# protection.net
KiCad netlist of a schematic drawn in Altium Designer
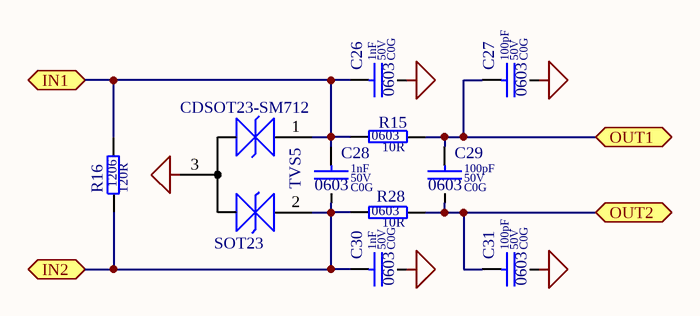
[diagram p0: protection.SchDoc]

(export (version "E")
  (design (tool "Eeschema 10.0.6"))
  (components
    (comp (ref "C26")
      (value "1nF")
      (footprint "C_0603_1608")
      (description "Capacitor")
      (fields
        (field (name "DIELECTRIC") "C0G")
        (field (name "VOLTAGE") "50V")
        (field (name "SCH_FOOTPRINT") "0603")
        (field (name "PART NUMBER") "C_1nF_50V_C0G_0603_5")
        (field (name "MANUFACTURER") "Samsung")
      )
      (libsource (lib "Library") (part "C"))
    )
    (comp (ref "C27")
      (value "100pF")
      (footprint "C_0603_1608")
      (description "Capacitor")
      (fields
        (field (name "DIELECTRIC") "C0G")
        (field (name "VOLTAGE") "50V")
        (field (name "SCH_FOOTPRINT") "0603")
        (field (name "PART NUMBER") "C_100pF_50V_C0G_0603_5")
        (field (name "MANUFACTURER") "AVX")
      )
      (libsource (lib "Library") (part "C"))
    )
    (comp (ref "C28")
      (value "1nF")
      (footprint "C_0603_1608")
      (description "Capacitor")
      (fields
        (field (name "DIELECTRIC") "C0G")
        (field (name "VOLTAGE") "50V")
        (field (name "SCH_FOOTPRINT") "0603")
        (field (name "PART NUMBER") "C_1nF_50V_C0G_0603_5")
        (field (name "MANUFACTURER") "Samsung")
      )
      (libsource (lib "Library") (part "C"))
    )
    (comp (ref "C29")
      (value "100pF")
      (footprint "C_0603_1608")
      (description "Capacitor")
      (fields
        (field (name "DIELECTRIC") "C0G")
        (field (name "VOLTAGE") "50V")
        (field (name "SCH_FOOTPRINT") "0603")
        (field (name "PART NUMBER") "C_100pF_50V_C0G_0603_5")
        (field (name "MANUFACTURER") "AVX")
      )
      (libsource (lib "Library") (part "C"))
    )
    (comp (ref "C30")
      (value "1nF")
      (footprint "C_0603_1608")
      (description "Capacitor")
      (fields
        (field (name "DIELECTRIC") "C0G")
        (field (name "VOLTAGE") "50V")
        (field (name "SCH_FOOTPRINT") "0603")
        (field (name "PART NUMBER") "C_1nF_50V_C0G_0603_5")
        (field (name "MANUFACTURER") "Samsung")
      )
      (libsource (lib "Library") (part "C"))
    )
    (comp (ref "C31")
      (value "100pF")
      (footprint "C_0603_1608")
      (description "Capacitor")
      (fields
        (field (name "DIELECTRIC") "C0G")
        (field (name "VOLTAGE") "50V")
        (field (name "SCH_FOOTPRINT") "0603")
        (field (name "PART NUMBER") "C_100pF_50V_C0G_0603_5")
        (field (name "MANUFACTURER") "AVX")
      )
      (libsource (lib "Library") (part "C"))
    )
    (comp (ref "R15")
      (value "10R")
      (footprint "R_0603_1608")
      (fields
        (field (name "SCH_FOOTPRINT") "0603")
        (field (name "PART NUMBER") "R_10R_0603_1")
        (field (name "VOLTAGE") "50V")
        (field (name "POWER") "100mW")
      )
      (libsource (lib "Library") (part "R"))
    )
    (comp (ref "R16")
      (value "120R")
      (footprint "R_1206_3216")
      (fields
        (field (name "SCH_FOOTPRINT") "1206")
        (field (name "PART NUMBER") "R_120R_1206_1")
        (field (name "VOLTAGE") "200V")
        (field (name "POWER") "250mW")
      )
      (libsource (lib "") (part "R_1"))
    )
    (comp (ref "R28")
      (value "10R")
      (footprint "R_0603_1608")
      (fields
        (field (name "SCH_FOOTPRINT") "0603")
        (field (name "PART NUMBER") "R_10R_0603_1")
        (field (name "VOLTAGE") "50V")
        (field (name "POWER") "100mW")
      )
      (libsource (lib "Library") (part "R"))
    )
    (comp (ref "TVS5")
      (value "CDSOT23-SM712")
      (footprint "SOT23_N")
      (fields
        (field (name "SCH_FOOTPRINT") "SOT23")
        (field (name "PART NUMBER") "TVS_CDSOT23-SM712")
        (field (name "VOLTAGE") "12V")
        (field (name "MANUFACTURER") "Bourns")
      )
      (libsource (lib "Library") (part "TVS_DOUBLE_BI_SOT23-3"))
    )
  )
  (nets
    (net (code "1") (name "/IN1") (class "Default")
      (node (ref "C26") (pin "1") (pinfunction "1_1") (pintype "passive"))
      (node (ref "C28") (pin "1") (pinfunction "1_1") (pintype "passive"))
      (node (ref "R15") (pin "2") (pinfunction "2_2") (pintype "bidirectional"))
      (node (ref "R16") (pin "2") (pinfunction "2_2") (pintype "passive"))
      (node (ref "TVS5") (pin "1") (pinfunction "1_1") (pintype "passive"))
    )
    (net (code "2") (name "/IN2") (class "Default")
      (node (ref "C28") (pin "2") (pinfunction "2_2") (pintype "passive"))
      (node (ref "C30") (pin "1") (pinfunction "1_1") (pintype "passive"))
      (node (ref "R16") (pin "1") (pinfunction "1_1") (pintype "passive"))
      (node (ref "R28") (pin "2") (pinfunction "2_2") (pintype "bidirectional"))
      (node (ref "TVS5") (pin "2") (pinfunction "2_2") (pintype "passive"))
    )
    (net (code "3") (name "/OUT1") (class "Default")
      (node (ref "C27") (pin "1") (pinfunction "1_1") (pintype "passive"))
      (node (ref "C29") (pin "1") (pinfunction "1_1") (pintype "passive"))
      (node (ref "R15") (pin "1") (pinfunction "1_1") (pintype "bidirectional"))
    )
    (net (code "4") (name "/OUT2") (class "Default")
      (node (ref "C29") (pin "2") (pinfunction "2_2") (pintype "passive"))
      (node (ref "C31") (pin "1") (pinfunction "1_1") (pintype "passive"))
      (node (ref "R28") (pin "1") (pinfunction "1_1") (pintype "bidirectional"))
    )
    (net (code "5") (name "GND") (class "Default")
      (node (ref "C26") (pin "2") (pinfunction "2_2") (pintype "passive"))
      (node (ref "C27") (pin "2") (pinfunction "2_2") (pintype "passive"))
      (node (ref "C30") (pin "2") (pinfunction "2_2") (pintype "passive"))
      (node (ref "C31") (pin "2") (pinfunction "2_2") (pintype "passive"))
      (node (ref "TVS5") (pin "3") (pinfunction "3_3") (pintype "passive"))
    )
  )
)
